# mbmc_io.net
KiCad netlist of a schematic drawn in EAGLE
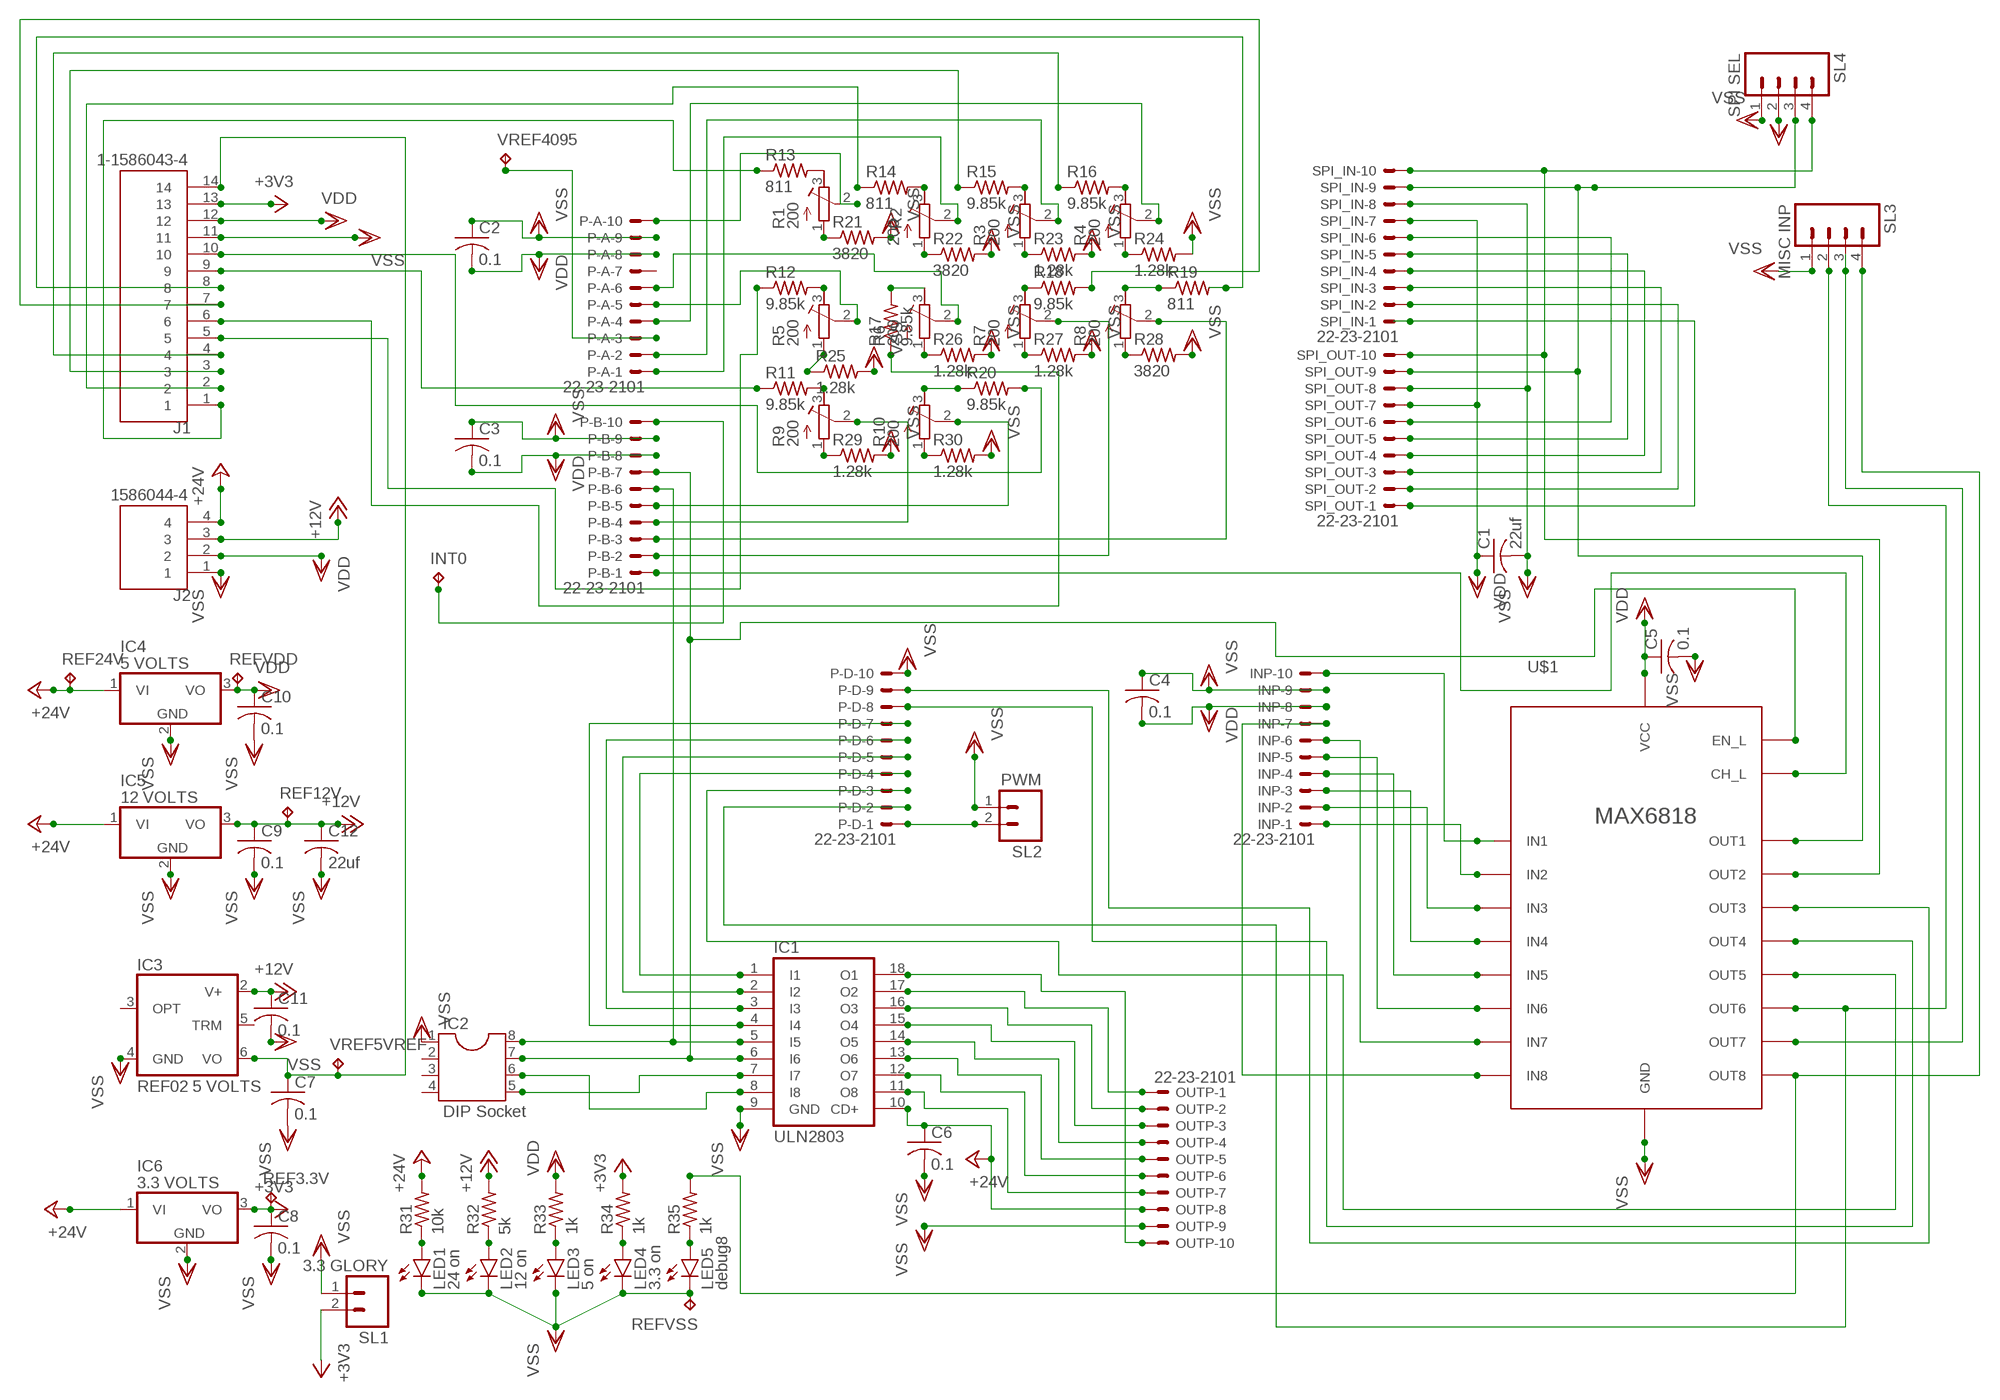
[diagram p0: schematic, sheet 1]

(export (version "E")
  (design (tool "Eeschema 10.0.6"))
  (components
    (comp (ref "C1")
      (value "22uf")
      (footprint "eagle-import:C0805")
      (libsource (lib "eagle-import") (part "C-USC0805"))
    )
    (comp (ref "C2")
      (value "0.1")
      (footprint "eagle-import:C0805")
      (libsource (lib "eagle-import") (part "C-USC0805"))
    )
    (comp (ref "C3")
      (value "0.1")
      (footprint "eagle-import:C0805")
      (libsource (lib "eagle-import") (part "C-USC0805"))
    )
    (comp (ref "C4")
      (value "0.1")
      (footprint "eagle-import:C0805")
      (libsource (lib "eagle-import") (part "C-USC0805"))
    )
    (comp (ref "C5")
      (value "0.1")
      (footprint "eagle-import:C0805")
      (libsource (lib "eagle-import") (part "C-USC0805"))
    )
    (comp (ref "C6")
      (value "0.1")
      (footprint "eagle-import:C0805")
      (libsource (lib "eagle-import") (part "C-USC0805"))
    )
    (comp (ref "C7")
      (value "0.1")
      (footprint "eagle-import:C0805")
      (libsource (lib "eagle-import") (part "C-USC0805"))
    )
    (comp (ref "C8")
      (value "0.1")
      (footprint "eagle-import:C0805")
      (libsource (lib "eagle-import") (part "C-USC0805"))
    )
    (comp (ref "C9")
      (value "0.1")
      (footprint "eagle-import:C0805")
      (libsource (lib "eagle-import") (part "C-USC0805"))
    )
    (comp (ref "C10")
      (value "0.1")
      (footprint "eagle-import:C0805")
      (libsource (lib "eagle-import") (part "C-USC0805"))
    )
    (comp (ref "C11")
      (value "0.1")
      (footprint "eagle-import:C0805")
      (libsource (lib "eagle-import") (part "C-USC0805"))
    )
    (comp (ref "C12")
      (value "22uf")
      (footprint "eagle-import:C0805")
      (libsource (lib "eagle-import") (part "C-USC0805"))
    )
    (comp (ref "IC1")
      (value "ULN2803")
      (footprint "eagle-import:DIL18")
      (libsource (lib "eagle-import") (part "ULN2803A"))
    )
    (comp (ref "IC2")
      (value "DIP Socket")
      (footprint "eagle-import:SOCKET-08")
      (libsource (lib "eagle-import") (part "DIL8S"))
    )
    (comp (ref "IC3")
      (value "REF02 5 VOLTS")
      (footprint "eagle-import:DIL08")
      (libsource (lib "eagle-import") (part "REF02Z"))
    )
    (comp (ref "IC4")
      (value "5 VOLTS")
      (footprint "eagle-import:TO220V")
      (libsource (lib "eagle-import") (part "78TV05"))
    )
    (comp (ref "IC5")
      (value "12 VOLTS")
      (footprint "eagle-import:TO220V")
      (libsource (lib "eagle-import") (part "78TV05"))
    )
    (comp (ref "IC6")
      (value "3.3 VOLTS")
      (footprint "eagle-import:TO220V")
      (libsource (lib "eagle-import") (part "78TV05"))
    )
    (comp (ref "INP")
      (value "22-23-2101")
      (footprint "eagle-import:22-23-2101")
      (fields (field (name "MF") "MOLEX"))
      (libsource (lib "eagle-import") (part "22-23-2101"))
    )
    (comp (ref "INT0")
      (value "TPB1,27")
      (footprint "eagle-import:B1,27")
      (libsource (lib "eagle-import") (part "TPB1,27"))
    )
    (comp (ref "J1")
      (value "1-1586043-4")
      (footprint "eagle-import:TE_1-1586043-4")
      (fields (field (name "MANUFACTURER") "TE"))
      (libsource (lib "eagle-import") (part "1-1586043-4"))
    )
    (comp (ref "J2")
      (value "1586044-4")
      (footprint "eagle-import:TE_1586044-4")
      (fields (field (name "MANUFACTURER") "TE"))
      (libsource (lib "eagle-import") (part "1586044-4"))
    )
    (comp (ref "LED1")
      (value "24 on")
      (footprint "eagle-import:CHIPLED_1206")
      (libsource (lib "eagle-import") (part "LEDCHIPLED_1206"))
    )
    (comp (ref "LED2")
      (value "12 on")
      (footprint "eagle-import:CHIPLED_1206")
      (libsource (lib "eagle-import") (part "LEDCHIPLED_1206"))
    )
    (comp (ref "LED3")
      (value "5 on")
      (footprint "eagle-import:CHIPLED_1206")
      (libsource (lib "eagle-import") (part "LEDCHIPLED_1206"))
    )
    (comp (ref "LED4")
      (value "3.3 on")
      (footprint "eagle-import:CHIPLED_1206")
      (libsource (lib "eagle-import") (part "LEDCHIPLED_1206"))
    )
    (comp (ref "LED5")
      (value "debug8")
      (footprint "eagle-import:CHIPLED_1206")
      (libsource (lib "eagle-import") (part "LEDCHIPLED_1206"))
    )
    (comp (ref "OUTP")
      (value "22-23-2101")
      (footprint "eagle-import:22-23-2101")
      (fields (field (name "MF") "MOLEX"))
      (libsource (lib "eagle-import") (part "22-23-2101"))
    )
    (comp (ref "P-A")
      (value "22-23-2101")
      (footprint "eagle-import:22-23-2101")
      (fields (field (name "MF") "MOLEX"))
      (libsource (lib "eagle-import") (part "22-23-2101"))
    )
    (comp (ref "P-B")
      (value "22-23-2101")
      (footprint "eagle-import:22-23-2101")
      (fields (field (name "MF") "MOLEX"))
      (libsource (lib "eagle-import") (part "22-23-2101"))
    )
    (comp (ref "P-D")
      (value "22-23-2101")
      (footprint "eagle-import:22-23-2101")
      (fields (field (name "MF") "MOLEX"))
      (libsource (lib "eagle-import") (part "22-23-2101"))
    )
    (comp (ref "R1")
      (value "200")
      (footprint "eagle-import:RTRIM3339P")
      (libsource (lib "eagle-import") (part "R-TRIMM3339P"))
    )
    (comp (ref "R2")
      (value "200")
      (footprint "eagle-import:RTRIM3339P")
      (libsource (lib "eagle-import") (part "R-TRIMM3339P"))
    )
    (comp (ref "R3")
      (value "200")
      (footprint "eagle-import:RTRIM3339P")
      (libsource (lib "eagle-import") (part "R-TRIMM3339P"))
    )
    (comp (ref "R4")
      (value "200")
      (footprint "eagle-import:RTRIM3339P")
      (libsource (lib "eagle-import") (part "R-TRIMM3339P"))
    )
    (comp (ref "R5")
      (value "200")
      (footprint "eagle-import:RTRIM3339P")
      (libsource (lib "eagle-import") (part "R-TRIMM3339P"))
    )
    (comp (ref "R6")
      (value "200")
      (footprint "eagle-import:RTRIM3339P")
      (libsource (lib "eagle-import") (part "R-TRIMM3339P"))
    )
    (comp (ref "R7")
      (value "200")
      (footprint "eagle-import:RTRIM3339P")
      (libsource (lib "eagle-import") (part "R-TRIMM3339P"))
    )
    (comp (ref "R8")
      (value "200")
      (footprint "eagle-import:RTRIM3339P")
      (libsource (lib "eagle-import") (part "R-TRIMM3339P"))
    )
    (comp (ref "R9")
      (value "200")
      (footprint "eagle-import:RTRIM3339P")
      (libsource (lib "eagle-import") (part "R-TRIMM3339P"))
    )
    (comp (ref "R10")
      (value "200")
      (footprint "eagle-import:RTRIM3339P")
      (libsource (lib "eagle-import") (part "R-TRIMM3339P"))
    )
    (comp (ref "R11")
      (value "9.85k")
      (footprint "eagle-import:R0805")
      (libsource (lib "eagle-import") (part "R-US_R0805"))
    )
    (comp (ref "R12")
      (value "9.85k")
      (footprint "eagle-import:R0805")
      (libsource (lib "eagle-import") (part "R-US_R0805"))
    )
    (comp (ref "R13")
      (value "811")
      (footprint "eagle-import:R0805")
      (libsource (lib "eagle-import") (part "R-US_R0805"))
    )
    (comp (ref "R14")
      (value "811")
      (footprint "eagle-import:R0805")
      (libsource (lib "eagle-import") (part "R-US_R0805"))
    )
    (comp (ref "R15")
      (value "9.85k")
      (footprint "eagle-import:R0805")
      (libsource (lib "eagle-import") (part "R-US_R0805"))
    )
    (comp (ref "R16")
      (value "9.85k")
      (footprint "eagle-import:R0805")
      (libsource (lib "eagle-import") (part "R-US_R0805"))
    )
    (comp (ref "R17")
      (value "9.85k")
      (footprint "eagle-import:R0805")
      (libsource (lib "eagle-import") (part "R-US_R0805"))
    )
    (comp (ref "R18")
      (value "9.85k")
      (footprint "eagle-import:R0805")
      (libsource (lib "eagle-import") (part "R-US_R0805"))
    )
    (comp (ref "R19")
      (value "811")
      (footprint "eagle-import:R0805")
      (libsource (lib "eagle-import") (part "R-US_R0805"))
    )
    (comp (ref "R20")
      (value "9.85k")
      (footprint "eagle-import:R0805")
      (libsource (lib "eagle-import") (part "R-US_R0805"))
    )
    (comp (ref "R21")
      (value "3820")
      (footprint "eagle-import:R0805")
      (libsource (lib "eagle-import") (part "R-US_R0805"))
    )
    (comp (ref "R22")
      (value "3820")
      (footprint "eagle-import:R0805")
      (libsource (lib "eagle-import") (part "R-US_R0805"))
    )
    (comp (ref "R23")
      (value "1.28k")
      (footprint "eagle-import:R0805")
      (libsource (lib "eagle-import") (part "R-US_R0805"))
    )
    (comp (ref "R24")
      (value "1.28k")
      (footprint "eagle-import:R0805")
      (libsource (lib "eagle-import") (part "R-US_R0805"))
    )
    (comp (ref "R25")
      (value "1.28k")
      (footprint "eagle-import:R0805")
      (libsource (lib "eagle-import") (part "R-US_R0805"))
    )
    (comp (ref "R26")
      (value "1.28k")
      (footprint "eagle-import:R0805")
      (libsource (lib "eagle-import") (part "R-US_R0805"))
    )
    (comp (ref "R27")
      (value "1.28k")
      (footprint "eagle-import:R0805")
      (libsource (lib "eagle-import") (part "R-US_R0805"))
    )
    (comp (ref "R28")
      (value "3820")
      (footprint "eagle-import:R0805")
      (libsource (lib "eagle-import") (part "R-US_R0805"))
    )
    (comp (ref "R29")
      (value "1.28k")
      (footprint "eagle-import:R0805")
      (libsource (lib "eagle-import") (part "R-US_R0805"))
    )
    (comp (ref "R30")
      (value "1.28k")
      (footprint "eagle-import:R0805")
      (libsource (lib "eagle-import") (part "R-US_R0805"))
    )
    (comp (ref "R31")
      (value "10k")
      (footprint "eagle-import:R0805")
      (libsource (lib "eagle-import") (part "R-US_R0805"))
    )
    (comp (ref "R32")
      (value "5k")
      (footprint "eagle-import:R0805")
      (libsource (lib "eagle-import") (part "R-US_R0805"))
    )
    (comp (ref "R33")
      (value "1k")
      (footprint "eagle-import:R0805")
      (libsource (lib "eagle-import") (part "R-US_R0805"))
    )
    (comp (ref "R34")
      (value "1k")
      (footprint "eagle-import:R0805")
      (libsource (lib "eagle-import") (part "R-US_R0805"))
    )
    (comp (ref "R35")
      (value "1k")
      (footprint "eagle-import:R0805")
      (libsource (lib "eagle-import") (part "R-US_R0805"))
    )
    (comp (ref "REF3.3V")
      (value "TPB1,27")
      (footprint "eagle-import:B1,27")
      (libsource (lib "eagle-import") (part "TPB1,27"))
    )
    (comp (ref "REF12V")
      (value "TPB1,27")
      (footprint "eagle-import:B1,27")
      (libsource (lib "eagle-import") (part "TPB1,27"))
    )
    (comp (ref "REF24V")
      (value "TPB1,27")
      (footprint "eagle-import:B1,27")
      (libsource (lib "eagle-import") (part "TPB1,27"))
    )
    (comp (ref "REFVDD")
      (value "TPB1,27")
      (footprint "eagle-import:B1,27")
      (libsource (lib "eagle-import") (part "TPB1,27"))
    )
    (comp (ref "REFVSS")
      (value "TPB1,27")
      (footprint "eagle-import:B1,27")
      (libsource (lib "eagle-import") (part "TPB1,27"))
    )
    (comp (ref "SL1")
      (value "3.3 GLORY")
      (footprint "eagle-import:02P")
      (libsource (lib "eagle-import") (part "M02"))
    )
    (comp (ref "SL2")
      (value "PWM")
      (footprint "eagle-import:02P")
      (libsource (lib "eagle-import") (part "M02"))
    )
    (comp (ref "SL3")
      (value "MISC INP")
      (footprint "eagle-import:04P")
      (libsource (lib "eagle-import") (part "M04"))
    )
    (comp (ref "SL4")
      (value "SPI SEL")
      (footprint "eagle-import:04P")
      (libsource (lib "eagle-import") (part "M04"))
    )
    (comp (ref "SPI_IN")
      (value "22-23-2101")
      (footprint "eagle-import:22-23-2101")
      (fields (field (name "MF") "MOLEX"))
      (libsource (lib "eagle-import") (part "22-23-2101"))
    )
    (comp (ref "SPI_OUT")
      (value "22-23-2101")
      (footprint "eagle-import:22-23-2101")
      (fields (field (name "MF") "MOLEX"))
      (libsource (lib "eagle-import") (part "22-23-2101"))
    )
    (comp (ref "U$1")
      (value "MAX6818")
      (footprint "eagle-import:SSOP20")
      (fields (field (name "MF") "Maxim Integrated"))
      (libsource (lib "eagle-import") (part "MAX6818"))
    )
    (comp (ref "VREF5VREF")
      (value "TPB1,27")
      (footprint "eagle-import:B1,27")
      (libsource (lib "eagle-import") (part "TPB1,27"))
    )
    (comp (ref "VREF4095")
      (value "TPB1,27")
      (footprint "eagle-import:B1,27")
      (libsource (lib "eagle-import") (part "TPB1,27"))
    )
  )
  (nets
    (net (code "1") (name "+3V3") (class "Default")
      (node (ref "C8") (pin "1") (pinfunction "1_1") (pintype "passive"))
      (node (ref "IC6") (pin "3") (pinfunction "VO_3") (pintype "passive"))
      (node (ref "J1") (pin "13") (pinfunction "13_13") (pintype "passive"))
      (node (ref "R34") (pin "2") (pinfunction "2_2") (pintype "passive"))
      (node (ref "REF3.3V") (pin "TP") (pinfunction "TP_TP") (pintype "input"))
      (node (ref "SL1") (pin "2") (pinfunction "2_2") (pintype "passive"))
    )
    (net (code "2") (name "+12V") (class "Default")
      (node (ref "C11") (pin "1") (pinfunction "1_1") (pintype "passive"))
      (node (ref "C12") (pin "1") (pinfunction "1_1") (pintype "passive"))
      (node (ref "C9") (pin "1") (pinfunction "1_1") (pintype "passive"))
      (node (ref "IC3") (pin "2") (pinfunction "V+_2") (pintype "power_in"))
      (node (ref "IC5") (pin "3") (pinfunction "VO_3") (pintype "passive"))
      (node (ref "J2") (pin "3") (pinfunction "3_3") (pintype "passive"))
      (node (ref "R32") (pin "2") (pinfunction "2_2") (pintype "passive"))
      (node (ref "REF12V") (pin "TP") (pinfunction "TP_TP") (pintype "input"))
    )
    (net (code "3") (name "+24V") (class "Default")
      (node (ref "C6") (pin "1") (pinfunction "1_1") (pintype "passive"))
      (node (ref "IC1") (pin "10") (pinfunction "CD+_10") (pintype "passive"))
      (node (ref "IC4") (pin "1") (pinfunction "VI_1") (pintype "input"))
      (node (ref "IC5") (pin "1") (pinfunction "VI_1") (pintype "input"))
      (node (ref "IC6") (pin "1") (pinfunction "VI_1") (pintype "input"))
      (node (ref "J2") (pin "4") (pinfunction "4_4") (pintype "passive"))
      (node (ref "OUTP") (pin "8") (pinfunction "S_8") (pintype "passive"))
      (node (ref "R31") (pin "2") (pinfunction "2_2") (pintype "passive"))
      (node (ref "REF24V") (pin "TP") (pinfunction "TP_TP") (pintype "input"))
    )
    (net (code "4") (name "Net-(IC1-I1)") (class "Default")
      (node (ref "IC1") (pin "1") (pinfunction "I1_1") (pintype "input"))
      (node (ref "P-D") (pin "4") (pinfunction "S_4") (pintype "passive"))
    )
    (net (code "5") (name "Net-(IC1-I2)") (class "Default")
      (node (ref "IC1") (pin "2") (pinfunction "I2_2") (pintype "input"))
      (node (ref "P-D") (pin "5") (pinfunction "S_5") (pintype "passive"))
    )
    (net (code "6") (name "Net-(IC1-I3)") (class "Default")
      (node (ref "IC1") (pin "3") (pinfunction "I3_3") (pintype "input"))
      (node (ref "P-D") (pin "6") (pinfunction "S_6") (pintype "passive"))
    )
    (net (code "7") (name "Net-(IC1-I4)") (class "Default")
      (node (ref "IC1") (pin "4") (pinfunction "I4_4") (pintype "input"))
      (node (ref "P-D") (pin "7") (pinfunction "S_7") (pintype "passive"))
    )
    (net (code "8") (name "Net-(IC1-I5)") (class "Default")
      (node (ref "IC1") (pin "5") (pinfunction "I5_5") (pintype "input"))
      (node (ref "IC2") (pin "8") (pinfunction "8_8") (pintype "passive"))
      (node (ref "P-B") (pin "6") (pinfunction "S_6") (pintype "passive"))
    )
    (net (code "9") (name "Net-(IC1-I6)") (class "Default")
      (node (ref "IC1") (pin "6") (pinfunction "I6_6") (pintype "input"))
      (node (ref "IC2") (pin "7") (pinfunction "7_7") (pintype "passive"))
      (node (ref "P-B") (pin "7") (pinfunction "S_7") (pintype "passive"))
      (node (ref "U$1") (pin "EN_L") (pinfunction "EN_L_EN_L") (pintype "bidirectional"))
    )
    (net (code "10") (name "Net-(IC1-I7)") (class "Default")
      (node (ref "IC1") (pin "7") (pinfunction "I7_7") (pintype "input"))
      (node (ref "IC2") (pin "5") (pinfunction "5_5") (pintype "passive"))
    )
    (net (code "11") (name "Net-(IC1-I8)") (class "Default")
      (node (ref "IC1") (pin "8") (pinfunction "I8_8") (pintype "input"))
      (node (ref "IC2") (pin "6") (pinfunction "6_6") (pintype "passive"))
    )
    (net (code "12") (name "Net-(IC1-O1)") (class "Default")
      (node (ref "IC1") (pin "18") (pinfunction "O1_18") (pintype "open_collector"))
      (node (ref "OUTP") (pin "10") (pinfunction "S_10") (pintype "passive"))
    )
    (net (code "13") (name "Net-(IC1-O2)") (class "Default")
      (node (ref "IC1") (pin "17") (pinfunction "O2_17") (pintype "open_collector"))
      (node (ref "OUTP") (pin "1") (pinfunction "S_1") (pintype "passive"))
    )
    (net (code "14") (name "Net-(IC1-O3)") (class "Default")
      (node (ref "IC1") (pin "16") (pinfunction "O3_16") (pintype "open_collector"))
      (node (ref "OUTP") (pin "2") (pinfunction "S_2") (pintype "passive"))
    )
    (net (code "15") (name "Net-(IC1-O4)") (class "Default")
      (node (ref "IC1") (pin "15") (pinfunction "O4_15") (pintype "open_collector"))
      (node (ref "OUTP") (pin "3") (pinfunction "S_3") (pintype "passive"))
    )
    (net (code "16") (name "Net-(IC1-O5)") (class "Default")
      (node (ref "IC1") (pin "14") (pinfunction "O5_14") (pintype "open_collector"))
      (node (ref "OUTP") (pin "4") (pinfunction "S_4") (pintype "passive"))
    )
    (net (code "17") (name "Net-(IC1-O6)") (class "Default")
      (node (ref "IC1") (pin "13") (pinfunction "O6_13") (pintype "open_collector"))
      (node (ref "OUTP") (pin "5") (pinfunction "S_5") (pintype "passive"))
    )
    (net (code "18") (name "Net-(IC1-O7)") (class "Default")
      (node (ref "IC1") (pin "12") (pinfunction "O7_12") (pintype "open_collector"))
      (node (ref "OUTP") (pin "6") (pinfunction "S_6") (pintype "passive"))
    )
    (net (code "19") (name "Net-(IC1-O8)") (class "Default")
      (node (ref "IC1") (pin "11") (pinfunction "O8_11") (pintype "open_collector"))
      (node (ref "OUTP") (pin "7") (pinfunction "S_7") (pintype "passive"))
    )
    (net (code "20") (name "Net-(IC3-VO)") (class "Default")
      (node (ref "C7") (pin "1") (pinfunction "1_1") (pintype "passive"))
      (node (ref "IC3") (pin "6") (pinfunction "VO_6") (pintype "output"))
      (node (ref "J1") (pin "14") (pinfunction "14_14") (pintype "passive"))
      (node (ref "VREF5VREF") (pin "TP") (pinfunction "TP_TP") (pintype "input"))
    )
    (net (code "21") (name "Net-(INPA-S)") (class "Default")
      (node (ref "INP") (pin "1") (pinfunction "S_1") (pintype "passive"))
      (node (ref "U$1") (pin "IN2") (pinfunction "IN2_IN2") (pintype "bidirectional"))
    )
    (net (code "22") (name "Net-(INPB-S)") (class "Default")
      (node (ref "INP") (pin "10") (pinfunction "S_10") (pintype "passive"))
      (node (ref "U$1") (pin "IN1") (pinfunction "IN1_IN1") (pintype "bidirectional"))
    )
    (net (code "23") (name "Net-(INPC-S)") (class "Default")
      (node (ref "INP") (pin "2") (pinfunction "S_2") (pintype "passive"))
      (node (ref "U$1") (pin "IN3") (pinfunction "IN3_IN3") (pintype "bidirectional"))
    )
    (net (code "24") (name "Net-(INPD-S)") (class "Default")
      (node (ref "INP") (pin "3") (pinfunction "S_3") (pintype "passive"))
      (node (ref "U$1") (pin "IN4") (pinfunction "IN4_IN4") (pintype "bidirectional"))
    )
    (net (code "25") (name "Net-(INPE-S)") (class "Default")
      (node (ref "INP") (pin "4") (pinfunction "S_4") (pintype "passive"))
      (node (ref "U$1") (pin "IN5") (pinfunction "IN5_IN5") (pintype "bidirectional"))
    )
    (net (code "26") (name "Net-(INPF-S)") (class "Default")
      (node (ref "INP") (pin "5") (pinfunction "S_5") (pintype "passive"))
      (node (ref "U$1") (pin "IN6") (pinfunction "IN6_IN6") (pintype "bidirectional"))
    )
    (net (code "27") (name "Net-(INPG-S)") (class "Default")
      (node (ref "INP") (pin "6") (pinfunction "S_6") (pintype "passive"))
      (node (ref "U$1") (pin "IN7") (pinfunction "IN7_IN7") (pintype "bidirectional"))
    )
    (net (code "28") (name "Net-(INPH-S)") (class "Default")
      (node (ref "INP") (pin "7") (pinfunction "S_7") (pintype "passive"))
      (node (ref "U$1") (pin "IN8") (pinfunction "IN8_IN8") (pintype "bidirectional"))
    )
    (net (code "29") (name "Net-(J1-Pad1)") (class "Default")
      (node (ref "J1") (pin "1") (pinfunction "1_1") (pintype "passive"))
      (node (ref "R13") (pin "1") (pinfunction "1_1") (pintype "passive"))
    )
    (net (code "30") (name "Net-(J1-Pad2)") (class "Default")
      (node (ref "J1") (pin "2") (pinfunction "2_2") (pintype "passive"))
      (node (ref "R14") (pin "1") (pinfunction "1_1") (pintype "passive"))
    )
    (net (code "31") (name "Net-(J1-Pad3)") (class "Default")
      (node (ref "J1") (pin "3") (pinfunction "3_3") (pintype "passive"))
      (node (ref "R15") (pin "1") (pinfunction "1_1") (pintype "passive"))
    )
    (net (code "32") (name "Net-(J1-Pad4)") (class "Default")
      (node (ref "J1") (pin "4") (pinfunction "4_4") (pintype "passive"))
      (node (ref "R16") (pin "1") (pinfunction "1_1") (pintype "passive"))
    )
    (net (code "33") (name "Net-(J1-Pad5)") (class "Default")
      (node (ref "J1") (pin "5") (pinfunction "5_5") (pintype "passive"))
      (node (ref "R12") (pin "1") (pinfunction "1_1") (pintype "passive"))
    )
    (net (code "34") (name "Net-(J1-Pad6)") (class "Default")
      (node (ref "J1") (pin "6") (pinfunction "6_6") (pintype "passive"))
      (node (ref "R17") (pin "1") (pinfunction "1_1") (pintype "passive"))
    )
    (net (code "35") (name "Net-(J1-Pad7)") (class "Default")
      (node (ref "J1") (pin "7") (pinfunction "7_7") (pintype "passive"))
      (node (ref "R18") (pin "2") (pinfunction "2_2") (pintype "passive"))
    )
    (net (code "36") (name "Net-(J1-Pad8)") (class "Default")
      (node (ref "J1") (pin "8") (pinfunction "8_8") (pintype "passive"))
      (node (ref "R19") (pin "2") (pinfunction "2_2") (pintype "passive"))
    )
    (net (code "37") (name "Net-(J1-Pad9)") (class "Default")
      (node (ref "J1") (pin "9") (pinfunction "9_9") (pintype "passive"))
      (node (ref "R11") (pin "1") (pinfunction "1_1") (pintype "passive"))
    )
    (net (code "38") (name "Net-(J1-Pad10)") (class "Default")
      (node (ref "J1") (pin "10") (pinfunction "10_10") (pintype "passive"))
      (node (ref "R20") (pin "2") (pinfunction "2_2") (pintype "passive"))
    )
    (net (code "39") (name "Net-(LED1-PadA)") (class "Default")
      (node (ref "LED1") (pin "A") (pinfunction "A_A") (pintype "passive"))
      (node (ref "R31") (pin "1") (pinfunction "1_1") (pintype "passive"))
    )
    (net (code "40") (name "Net-(LED2-PadA)") (class "Default")
      (node (ref "LED2") (pin "A") (pinfunction "A_A") (pintype "passive"))
      (node (ref "R32") (pin "1") (pinfunction "1_1") (pintype "passive"))
    )
    (net (code "41") (name "Net-(LED3-PadA)") (class "Default")
      (node (ref "LED3") (pin "A") (pinfunction "A_A") (pintype "passive"))
      (node (ref "R33") (pin "1") (pinfunction "1_1") (pintype "passive"))
    )
    (net (code "42") (name "Net-(LED4-PadA)") (class "Default")
      (node (ref "LED4") (pin "A") (pinfunction "A_A") (pintype "passive"))
      (node (ref "R34") (pin "1") (pinfunction "1_1") (pintype "passive"))
    )
    (net (code "43") (name "Net-(LED5-PadA)") (class "Default")
      (node (ref "LED5") (pin "A") (pinfunction "A_A") (pintype "passive"))
      (node (ref "R35") (pin "1") (pinfunction "1_1") (pintype "passive"))
    )
    (net (code "44") (name "Net-(P-AA-S)") (class "Default")
      (node (ref "P-A") (pin "1") (pinfunction "S_1") (pintype "passive"))
      (node (ref "R2") (pin "2") (pinfunction "S_2") (pintype "passive"))
    )
    (net (code "45") (name "Net-(P-AB-S)") (class "Default")
      (node (ref "P-A") (pin "10") (pinfunction "S_10") (pintype "passive"))
      (node (ref "R1") (pin "2") (pinfunction "S_2") (pintype "passive"))
    )
    (net (code "46") (name "Net-(P-AC-S)") (class "Default")
      (node (ref "P-A") (pin "2") (pinfunction "S_2") (pintype "passive"))
      (node (ref "R3") (pin "2") (pinfunction "S_2") (pintype "passive"))
    )
    (net (code "47") (name "Net-(P-AD-S)") (class "Default")
      (node (ref "P-A") (pin "3") (pinfunction "S_3") (pintype "passive"))
      (node (ref "VREF4095") (pin "TP") (pinfunction "TP_TP") (pintype "input"))
    )
    (net (code "48") (name "Net-(P-AE-S)") (class "Default")
      (node (ref "P-A") (pin "4") (pinfunction "S_4") (pintype "passive"))
      (node (ref "R4") (pin "2") (pinfunction "S_2") (pintype "passive"))
    )
    (net (code "49") (name "Net-(P-AF-S)") (class "Default")
      (node (ref "P-A") (pin "5") (pinfunction "S_5") (pintype "passive"))
      (node (ref "R5") (pin "2") (pinfunction "S_2") (pintype "passive"))
    )
    (net (code "50") (name "Net-(P-AG-S)") (class "Default")
      (node (ref "P-A") (pin "6") (pinfunction "S_6") (pintype "passive"))
      (node (ref "R6") (pin "2") (pinfunction "S_2") (pintype "passive"))
    )
    (net (code "51") (name "Net-(P-BA-S)") (class "Default")
      (node (ref "P-B") (pin "1") (pinfunction "S_1") (pintype "passive"))
      (node (ref "U$1") (pin "CH_L") (pinfunction "CH_L_CH_L") (pintype "bidirectional"))
    )
    (net (code "52") (name "Net-(P-BB-S)") (class "Default")
      (node (ref "INT0") (pin "TP") (pinfunction "TP_TP") (pintype "input"))
      (node (ref "P-B") (pin "10") (pinfunction "S_10") (pintype "passive"))
    )
    (net (code "53") (name "Net-(P-BC-S)") (class "Default")
      (node (ref "P-B") (pin "2") (pinfunction "S_2") (pintype "passive"))
      (node (ref "R7") (pin "2") (pinfunction "S_2") (pintype "passive"))
    )
    (net (code "54") (name "Net-(P-BD-S)") (class "Default")
      (node (ref "P-B") (pin "3") (pinfunction "S_3") (pintype "passive"))
      (node (ref "R8") (pin "2") (pinfunction "S_2") (pintype "passive"))
    )
    (net (code "55") (name "Net-(P-BE-S)") (class "Default")
      (node (ref "P-B") (pin "4") (pinfunction "S_4") (pintype "passive"))
      (node (ref "R9") (pin "2") (pinfunction "S_2") (pintype "passive"))
    )
    (net (code "56") (name "Net-(P-BF-S)") (class "Default")
      (node (ref "P-B") (pin "5") (pinfunction "S_5") (pintype "passive"))
      (node (ref "R10") (pin "2") (pinfunction "S_2") (pintype "passive"))
    )
    (net (code "57") (name "Net-(P-DA-S)") (class "Default")
      (node (ref "P-D") (pin "1") (pinfunction "S_1") (pintype "passive"))
      (node (ref "SL2") (pin "2") (pinfunction "2_2") (pintype "passive"))
    )
    (net (code "58") (name "Net-(P-DC-S)") (class "Default")
      (node (ref "P-D") (pin "2") (pinfunction "S_2") (pintype "passive"))
      (node (ref "SL3") (pin "2") (pinfunction "2_2") (pintype "passive"))
      (node (ref "U$1") (pin "OUT6") (pinfunction "OUT6_OUT6") (pintype "bidirectional"))
    )
    (net (code "59") (name "Net-(P-DD-S)") (class "Default")
      (node (ref "P-D") (pin "3") (pinfunction "S_3") (pintype "passive"))
      (node (ref "U$1") (pin "OUT5") (pinfunction "OUT5_OUT5") (pintype "bidirectional"))
    )
    (net (code "60") (name "Net-(P-DI-S)") (class "Default")
      (node (ref "P-D") (pin "8") (pinfunction "S_8") (pintype "passive"))
      (node (ref "U$1") (pin "OUT4") (pinfunction "OUT4_OUT4") (pintype "bidirectional"))
    )
    (net (code "61") (name "Net-(P-DJ-S)") (class "Default")
      (node (ref "P-D") (pin "9") (pinfunction "S_9") (pintype "passive"))
      (node (ref "U$1") (pin "OUT3") (pinfunction "OUT3_OUT3") (pintype "bidirectional"))
    )
    (net (code "62") (name "Net-(R1-A)") (class "Default")
      (node (ref "R1") (pin "1") (pinfunction "A_1") (pintype "passive"))
      (node (ref "R21") (pin "1") (pinfunction "1_1") (pintype "passive"))
    )
    (net (code "63") (name "Net-(R1-E)") (class "Default")
      (node (ref "R1") (pin "3") (pinfunction "E_3") (pintype "passive"))
      (node (ref "R13") (pin "2") (pinfunction "2_2") (pintype "passive"))
    )
    (net (code "64") (name "Net-(R2-A)") (class "Default")
      (node (ref "R2") (pin "1") (pinfunction "A_1") (pintype "passive"))
      (node (ref "R22") (pin "1") (pinfunction "1_1") (pintype "passive"))
    )
    (net (code "65") (name "Net-(R2-E)") (class "Default")
      (node (ref "R14") (pin "2") (pinfunction "2_2") (pintype "passive"))
      (node (ref "R2") (pin "3") (pinfunction "E_3") (pintype "passive"))
    )
    (net (code "66") (name "Net-(R3-A)") (class "Default")
      (node (ref "R23") (pin "1") (pinfunction "1_1") (pintype "passive"))
      (node (ref "R3") (pin "1") (pinfunction "A_1") (pintype "passive"))
    )
    (net (code "67") (name "Net-(R3-E)") (class "Default")
      (node (ref "R15") (pin "2") (pinfunction "2_2") (pintype "passive"))
      (node (ref "R3") (pin "3") (pinfunction "E_3") (pintype "passive"))
    )
    (net (code "68") (name "Net-(R4-A)") (class "Default")
      (node (ref "R24") (pin "1") (pinfunction "1_1") (pintype "passive"))
      (node (ref "R4") (pin "1") (pinfunction "A_1") (pintype "passive"))
    )
    (net (code "69") (name "Net-(R4-E)") (class "Default")
      (node (ref "R16") (pin "2") (pinfunction "2_2") (pintype "passive"))
      (node (ref "R4") (pin "3") (pinfunction "E_3") (pintype "passive"))
    )
    (net (code "70") (name "Net-(R5-A)") (class "Default")
      (node (ref "R25") (pin "1") (pinfunction "1_1") (pintype "passive"))
      (node (ref "R5") (pin "1") (pinfunction "A_1") (pintype "passive"))
    )
    (net (code "71") (name "Net-(R5-E)") (class "Default")
      (node (ref "R12") (pin "2") (pinfunction "2_2") (pintype "passive"))
      (node (ref "R5") (pin "3") (pinfunction "E_3") (pintype "passive"))
    )
    (net (code "72") (name "Net-(R6-A)") (class "Default")
      (node (ref "R26") (pin "1") (pinfunction "1_1") (pintype "passive"))
      (node (ref "R6") (pin "1") (pinfunction "A_1") (pintype "passive"))
    )
    (net (code "73") (name "Net-(R6-E)") (class "Default")
      (node (ref "R17") (pin "2") (pinfunction "2_2") (pintype "passive"))
      (node (ref "R6") (pin "3") (pinfunction "E_3") (pintype "passive"))
    )
    (net (code "74") (name "Net-(R7-A)") (class "Default")
      (node (ref "R27") (pin "1") (pinfunction "1_1") (pintype "passive"))
      (node (ref "R7") (pin "1") (pinfunction "A_1") (pintype "passive"))
    )
    (net (code "75") (name "Net-(R7-E)") (class "Default")
      (node (ref "R18") (pin "1") (pinfunction "1_1") (pintype "passive"))
      (node (ref "R7") (pin "3") (pinfunction "E_3") (pintype "passive"))
    )
    (net (code "76") (name "Net-(R8-A)") (class "Default")
      (node (ref "R28") (pin "1") (pinfunction "1_1") (pintype "passive"))
      (node (ref "R8") (pin "1") (pinfunction "A_1") (pintype "passive"))
    )
    (net (code "77") (name "Net-(R8-E)") (class "Default")
      (node (ref "R19") (pin "1") (pinfunction "1_1") (pintype "passive"))
      (node (ref "R8") (pin "3") (pinfunction "E_3") (pintype "passive"))
    )
    (net (code "78") (name "Net-(R9-A)") (class "Default")
      (node (ref "R29") (pin "1") (pinfunction "1_1") (pintype "passive"))
      (node (ref "R9") (pin "1") (pinfunction "A_1") (pintype "passive"))
    )
    (net (code "79") (name "Net-(R9-E)") (class "Default")
      (node (ref "R11") (pin "2") (pinfunction "2_2") (pintype "passive"))
      (node (ref "R9") (pin "3") (pinfunction "E_3") (pintype "passive"))
    )
    (net (code "80") (name "Net-(R10-A)") (class "Default")
      (node (ref "R10") (pin "1") (pinfunction "A_1") (pintype "passive"))
      (node (ref "R30") (pin "1") (pinfunction "1_1") (pintype "passive"))
    )
    (net (code "81") (name "Net-(R10-E)") (class "Default")
      (node (ref "R10") (pin "3") (pinfunction "E_3") (pintype "passive"))
      (node (ref "R20") (pin "1") (pinfunction "1_1") (pintype "passive"))
    )
    (net (code "82") (name "Net-(R35-Pad2)") (class "Default")
      (node (ref "R35") (pin "2") (pinfunction "2_2") (pintype "passive"))
      (node (ref "SL3") (pin "4") (pinfunction "4_4") (pintype "passive"))
      (node (ref "U$1") (pin "OUT8") (pinfunction "OUT8_OUT8") (pintype "bidirectional"))
    )
    (net (code "83") (name "Net-(SL3-Pad3)") (class "Default")
      (node (ref "SL3") (pin "3") (pinfunction "3_3") (pintype "passive"))
      (node (ref "U$1") (pin "OUT7") (pinfunction "OUT7_OUT7") (pintype "bidirectional"))
    )
    (net (code "84") (name "Net-(SPI_INA-S)") (class "Default")
      (node (ref "SPI_IN") (pin "1") (pinfunction "S_1") (pintype "passive"))
      (node (ref "SPI_OUT") (pin "1") (pinfunction "S_1") (pintype "passive"))
    )
    (net (code "85") (name "Net-(SPI_INB-S)") (class "Default")
      (node (ref "SL4") (pin "4") (pinfunction "4_4") (pintype "passive"))
      (node (ref "SPI_IN") (pin "10") (pinfunction "S_10") (pintype "passive"))
      (node (ref "SPI_OUT") (pin "10") (pinfunction "S_10") (pintype "passive"))
      (node (ref "U$1") (pin "OUT2") (pinfunction "OUT2_OUT2") (pintype "bidirectional"))
    )
    (net (code "86") (name "Net-(SPI_INC-S)") (class "Default")
      (node (ref "SPI_IN") (pin "2") (pinfunction "S_2") (pintype "passive"))
      (node (ref "SPI_OUT") (pin "2") (pinfunction "S_2") (pintype "passive"))
    )
    (net (code "87") (name "Net-(SPI_IND-S)") (class "Default")
      (node (ref "SPI_IN") (pin "3") (pinfunction "S_3") (pintype "passive"))
      (node (ref "SPI_OUT") (pin "3") (pinfunction "S_3") (pintype "passive"))
    )
    (net (code "88") (name "Net-(SPI_INE-S)") (class "Default")
      (node (ref "SPI_IN") (pin "4") (pinfunction "S_4") (pintype "passive"))
      (node (ref "SPI_OUT") (pin "4") (pinfunction "S_4") (pintype "passive"))
    )
    (net (code "89") (name "Net-(SPI_INF-S)") (class "Default")
      (node (ref "SPI_IN") (pin "5") (pinfunction "S_5") (pintype "passive"))
      (node (ref "SPI_OUT") (pin "5") (pinfunction "S_5") (pintype "passive"))
    )
    (net (code "90") (name "Net-(SPI_ING-S)") (class "Default")
      (node (ref "SPI_IN") (pin "6") (pinfunction "S_6") (pintype "passive"))
      (node (ref "SPI_OUT") (pin "6") (pinfunction "S_6") (pintype "passive"))
    )
    (net (code "91") (name "Net-(SPI_INJ-S)") (class "Default")
      (node (ref "SL4") (pin "3") (pinfunction "3_3") (pintype "passive"))
      (node (ref "SPI_IN") (pin "9") (pinfunction "S_9") (pintype "passive"))
      (node (ref "SPI_OUT") (pin "9") (pinfunction "S_9") (pintype "passive"))
      (node (ref "U$1") (pin "OUT1") (pinfunction "OUT1_OUT1") (pintype "bidirectional"))
    )
    (net (code "92") (name "VDD") (class "Default")
      (node (ref "C1") (pin "1") (pinfunction "1_1") (pintype "passive"))
      (node (ref "C10") (pin "1") (pinfunction "1_1") (pintype "passive"))
      (node (ref "C2") (pin "2") (pinfunction "2_2") (pintype "passive"))
      (node (ref "C3") (pin "2") (pinfunction "2_2") (pintype "passive"))
      (node (ref "C4") (pin "2") (pinfunction "2_2") (pintype "passive"))
      (node (ref "C5") (pin "1") (pinfunction "1_1") (pintype "passive"))
      (node (ref "IC4") (pin "3") (pinfunction "VO_3") (pintype "passive"))
      (node (ref "INP") (pin "8") (pinfunction "S_8") (pintype "passive"))
      (node (ref "J1") (pin "12") (pinfunction "12_12") (pintype "passive"))
      (node (ref "J2") (pin "2") (pinfunction "2_2") (pintype "passive"))
      (node (ref "P-A") (pin "8") (pinfunction "S_8") (pintype "passive"))
      (node (ref "P-B") (pin "8") (pinfunction "S_8") (pintype "passive"))
      (node (ref "R33") (pin "2") (pinfunction "2_2") (pintype "passive"))
      (node (ref "REFVDD") (pin "TP") (pinfunction "TP_TP") (pintype "input"))
      (node (ref "SL4") (pin "2") (pinfunction "2_2") (pintype "passive"))
      (node (ref "SPI_IN") (pin "7") (pinfunction "S_7") (pintype "passive"))
      (node (ref "SPI_OUT") (pin "7") (pinfunction "S_7") (pintype "passive"))
      (node (ref "U$1") (pin "VCC") (pinfunction "VCC_VCC") (pintype "bidirectional"))
    )
    (net (code "93") (name "VSS") (class "Default")
      (node (ref "C1") (pin "2") (pinfunction "2_2") (pintype "passive"))
      (node (ref "C10") (pin "2") (pinfunction "2_2") (pintype "passive"))
      (node (ref "C11") (pin "2") (pinfunction "2_2") (pintype "passive"))
      (node (ref "C12") (pin "2") (pinfunction "2_2") (pintype "passive"))
      (node (ref "C2") (pin "1") (pinfunction "1_1") (pintype "passive"))
      (node (ref "C3") (pin "1") (pinfunction "1_1") (pintype "passive"))
      (node (ref "C4") (pin "1") (pinfunction "1_1") (pintype "passive"))
      (node (ref "C5") (pin "2") (pinfunction "2_2") (pintype "passive"))
      (node (ref "C6") (pin "2") (pinfunction "2_2") (pintype "passive"))
      (node (ref "C7") (pin "2") (pinfunction "2_2") (pintype "passive"))
      (node (ref "C8") (pin "2") (pinfunction "2_2") (pintype "passive"))
      (node (ref "C9") (pin "2") (pinfunction "2_2") (pintype "passive"))
      (node (ref "IC1") (pin "9") (pinfunction "GND_9") (pintype "power_in"))
      (node (ref "IC2") (pin "1") (pinfunction "1_1") (pintype "passive"))
      (node (ref "IC3") (pin "4") (pinfunction "GND_4") (pintype "power_in"))
      (node (ref "IC4") (pin "2") (pinfunction "GND_2") (pintype "passive"))
      (node (ref "IC5") (pin "2") (pinfunction "GND_2") (pintype "passive"))
      (node (ref "IC6") (pin "2") (pinfunction "GND_2") (pintype "passive"))
      (node (ref "INP") (pin "9") (pinfunction "S_9") (pintype "passive"))
      (node (ref "J1") (pin "11") (pinfunction "11_11") (pintype "passive"))
      (node (ref "J2") (pin "1") (pinfunction "1_1") (pintype "passive"))
      (node (ref "LED1") (pin "C") (pinfunction "C_C") (pintype "passive"))
      (node (ref "LED2") (pin "C") (pinfunction "C_C") (pintype "passive"))
      (node (ref "LED3") (pin "C") (pinfunction "C_C") (pintype "passive"))
      (node (ref "LED4") (pin "C") (pinfunction "C_C") (pintype "passive"))
      (node (ref "LED5") (pin "C") (pinfunction "C_C") (pintype "passive"))
      (node (ref "OUTP") (pin "9") (pinfunction "S_9") (pintype "passive"))
      (node (ref "P-A") (pin "9") (pinfunction "S_9") (pintype "passive"))
      (node (ref "P-B") (pin "9") (pinfunction "S_9") (pintype "passive"))
      (node (ref "P-D") (pin "10") (pinfunction "S_10") (pintype "passive"))
      (node (ref "R21") (pin "2") (pinfunction "2_2") (pintype "passive"))
      (node (ref "R22") (pin "2") (pinfunction "2_2") (pintype "passive"))
      (node (ref "R23") (pin "2") (pinfunction "2_2") (pintype "passive"))
      (node (ref "R24") (pin "2") (pinfunction "2_2") (pintype "passive"))
      (node (ref "R25") (pin "2") (pinfunction "2_2") (pintype "passive"))
      (node (ref "R26") (pin "2") (pinfunction "2_2") (pintype "passive"))
      (node (ref "R27") (pin "2") (pinfunction "2_2") (pintype "passive"))
      (node (ref "R28") (pin "2") (pinfunction "2_2") (pintype "passive"))
      (node (ref "R29") (pin "2") (pinfunction "2_2") (pintype "passive"))
      (node (ref "R30") (pin "2") (pinfunction "2_2") (pintype "passive"))
      (node (ref "REFVSS") (pin "TP") (pinfunction "TP_TP") (pintype "input"))
      (node (ref "SL1") (pin "1") (pinfunction "1_1") (pintype "passive"))
      (node (ref "SL2") (pin "1") (pinfunction "1_1") (pintype "passive"))
      (node (ref "SL3") (pin "1") (pinfunction "1_1") (pintype "passive"))
      (node (ref "SL4") (pin "1") (pinfunction "1_1") (pintype "passive"))
      (node (ref "SPI_IN") (pin "8") (pinfunction "S_8") (pintype "passive"))
      (node (ref "SPI_OUT") (pin "8") (pinfunction "S_8") (pintype "passive"))
      (node (ref "U$1") (pin "GND") (pinfunction "GND_GND") (pintype "bidirectional"))
    )
    (net (code "94") (name "unconnected-(IC2-Pad2)") (class "Default")
      (node (ref "IC2") (pin "2") (pinfunction "2_2") (pintype "passive"))
    )
    (net (code "95") (name "unconnected-(IC2-Pad3)") (class "Default")
      (node (ref "IC2") (pin "3") (pinfunction "3_3") (pintype "passive"))
    )
    (net (code "96") (name "unconnected-(IC2-Pad4)") (class "Default")
      (node (ref "IC2") (pin "4") (pinfunction "4_4") (pintype "passive"))
    )
    (net (code "97") (name "unconnected-(IC3-OPT-Pad3)") (class "Default")
      (node (ref "IC3") (pin "3") (pinfunction "OPT_3") (pintype "output"))
    )
    (net (code "98") (name "unconnected-(IC3-TRM-Pad5)") (class "Default")
      (node (ref "IC3") (pin "5") (pinfunction "TRM_5") (pintype "input"))
    )
    (net (code "99") (name "unconnected-(P-AH-S-Pad7)") (class "Default")
      (node (ref "P-A") (pin "7") (pinfunction "S_7") (pintype "passive"))
    )
  )
)
